# cap_touch.net
KiCad netlist of a schematic drawn in EAGLE
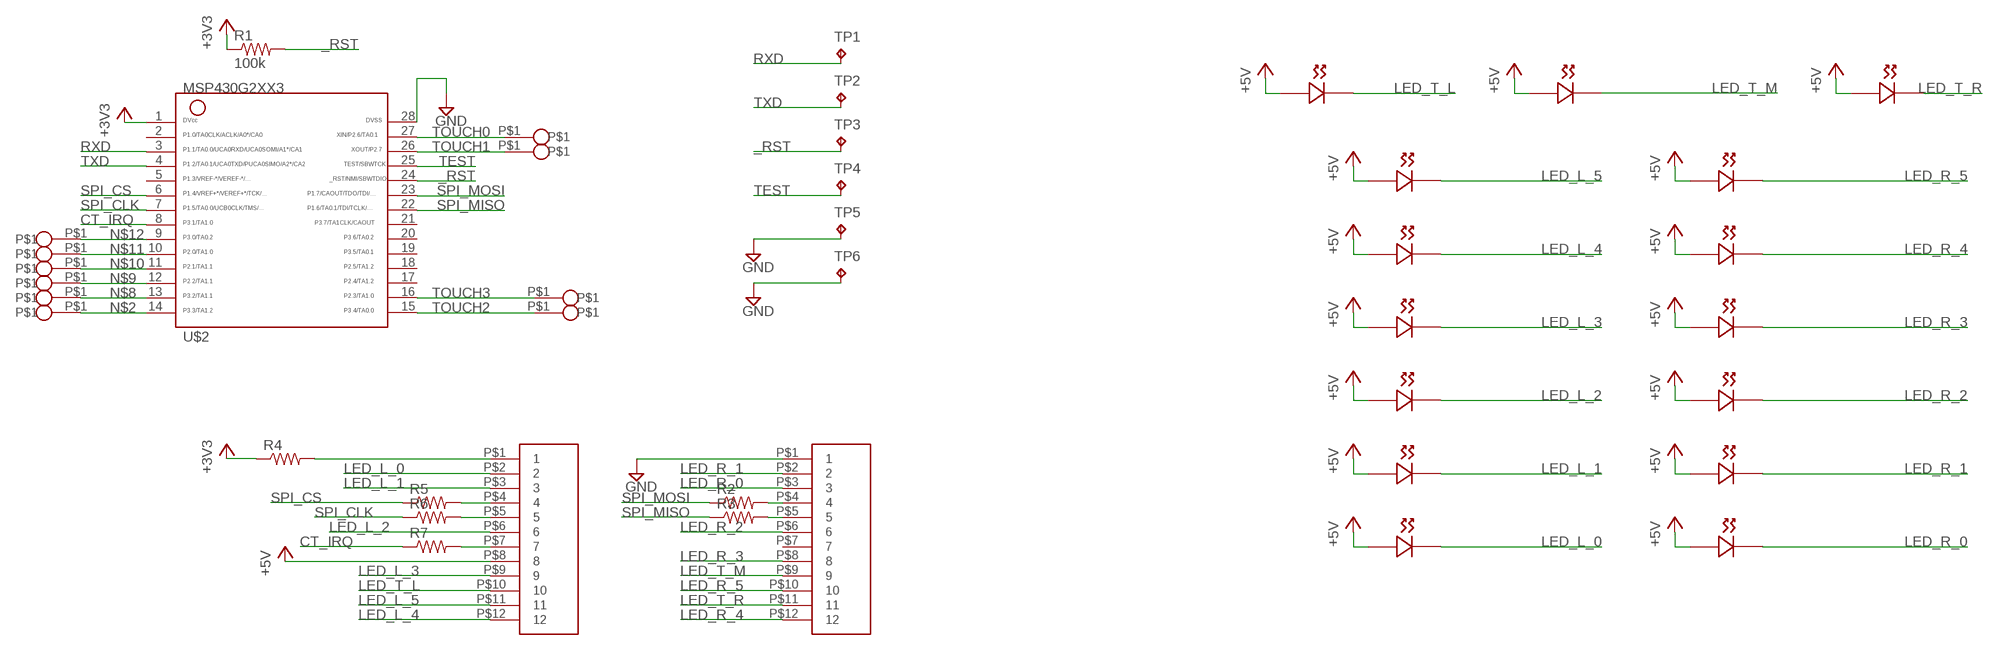
[diagram p0: schematic, sheet 1]

(export (version "E")
  (design (tool "Eeschema 10.0.6"))
  (components
    (comp (ref "R1")
      (value "100k")
      (footprint "eagle-import:0603-RES")
      (libsource (lib "eagle-import") (part "RESISTOR0603-RES"))
    )
    (comp (ref "R2")
      (value "RESISTOR0805-RES")
      (footprint "eagle-import:0805")
      (libsource (lib "eagle-import") (part "SparkFun-Resistors_RESISTOR0805-RES"))
    )
    (comp (ref "R3")
      (value "RESISTOR0805-RES")
      (footprint "eagle-import:0805")
      (libsource (lib "eagle-import") (part "SparkFun-Resistors_RESISTOR0805-RES"))
    )
    (comp (ref "R4")
      (value "RESISTOR0805-RES")
      (footprint "eagle-import:0805")
      (libsource (lib "eagle-import") (part "SparkFun-Resistors_RESISTOR0805-RES"))
    )
    (comp (ref "R5")
      (value "RESISTOR0805-RES")
      (footprint "eagle-import:0805")
      (libsource (lib "eagle-import") (part "SparkFun-Resistors_RESISTOR0805-RES"))
    )
    (comp (ref "R6")
      (value "RESISTOR0805-RES")
      (footprint "eagle-import:0805")
      (libsource (lib "eagle-import") (part "SparkFun-Resistors_RESISTOR0805-RES"))
    )
    (comp (ref "R7")
      (value "RESISTOR0805-RES")
      (footprint "eagle-import:0805")
      (libsource (lib "eagle-import") (part "SparkFun-Resistors_RESISTOR0805-RES"))
    )
    (comp (ref "TP1")
      (value "TPTP18SQ")
      (footprint "eagle-import:TP18SQ")
      (libsource (lib "eagle-import") (part "TPTP18SQ"))
    )
    (comp (ref "TP2")
      (value "TPTP18SQ")
      (footprint "eagle-import:TP18SQ")
      (libsource (lib "eagle-import") (part "TPTP18SQ"))
    )
    (comp (ref "TP3")
      (value "TPTP18SQ")
      (footprint "eagle-import:TP18SQ")
      (libsource (lib "eagle-import") (part "TPTP18SQ"))
    )
    (comp (ref "TP4")
      (value "TPTP18SQ")
      (footprint "eagle-import:TP18SQ")
      (libsource (lib "eagle-import") (part "TPTP18SQ"))
    )
    (comp (ref "TP5")
      (value "TPTP18SQ")
      (footprint "eagle-import:TP18SQ")
      (libsource (lib "eagle-import") (part "TPTP18SQ"))
    )
    (comp (ref "TP6")
      (value "TPTP18SQ")
      (footprint "eagle-import:TP18SQ")
      (libsource (lib "eagle-import") (part "TPTP18SQ"))
    )
    (comp (ref "U$1")
      (value "12_PIN_SMT_HEADER")
      (footprint "eagle-import:SMT_12PIN_HEADER")
      (libsource (lib "eagle-import") (part "12_PIN_SMT_HEADER"))
    )
    (comp (ref "U$2")
      (value "G2XX3---PW28")
      (footprint "eagle-import:PW28")
      (libsource (lib "eagle-import") (part "G2XX3---PW28"))
    )
    (comp (ref "U$3")
      (value "12_PIN_SMT_HEADER")
      (footprint "eagle-import:SMT_12PIN_HEADER")
      (libsource (lib "eagle-import") (part "12_PIN_SMT_HEADER"))
    )
    (comp (ref "U$8")
      (value "597-6601-607F")
      (footprint "eagle-import:597-6601-607F")
      (libsource (lib "eagle-import") (part "597-6601-607F"))
    )
    (comp (ref "U$9")
      (value "597-6601-607F")
      (footprint "eagle-import:597-6601-607F")
      (libsource (lib "eagle-import") (part "597-6601-607F"))
    )
    (comp (ref "U$10")
      (value "597-6601-607F")
      (footprint "eagle-import:597-6601-607F")
      (libsource (lib "eagle-import") (part "597-6601-607F"))
    )
    (comp (ref "U$11")
      (value "597-6601-607F")
      (footprint "eagle-import:597-6601-607F")
      (libsource (lib "eagle-import") (part "597-6601-607F"))
    )
    (comp (ref "U$12")
      (value "597-6601-607F")
      (footprint "eagle-import:597-6601-607F")
      (libsource (lib "eagle-import") (part "597-6601-607F"))
    )
    (comp (ref "U$13")
      (value "597-6601-607F")
      (footprint "eagle-import:597-6601-607F")
      (libsource (lib "eagle-import") (part "597-6601-607F"))
    )
    (comp (ref "U$14")
      (value "597-6601-607F")
      (footprint "eagle-import:597-6601-607F")
      (libsource (lib "eagle-import") (part "597-6601-607F"))
    )
    (comp (ref "U$15")
      (value "597-6601-607F")
      (footprint "eagle-import:597-6601-607F")
      (libsource (lib "eagle-import") (part "597-6601-607F"))
    )
    (comp (ref "U$16")
      (value "597-6601-607F")
      (footprint "eagle-import:597-6601-607F")
      (libsource (lib "eagle-import") (part "597-6601-607F"))
    )
    (comp (ref "U$17")
      (value "597-6601-607F")
      (footprint "eagle-import:597-6601-607F")
      (libsource (lib "eagle-import") (part "597-6601-607F"))
    )
    (comp (ref "U$18")
      (value "597-6601-607F")
      (footprint "eagle-import:597-6601-607F")
      (libsource (lib "eagle-import") (part "597-6601-607F"))
    )
    (comp (ref "U$19")
      (value "597-6601-607F")
      (footprint "eagle-import:597-6601-607F")
      (libsource (lib "eagle-import") (part "597-6601-607F"))
    )
    (comp (ref "U$20")
      (value "597-6601-607F")
      (footprint "eagle-import:597-6601-607F")
      (libsource (lib "eagle-import") (part "597-6601-607F"))
    )
    (comp (ref "U$21")
      (value "597-6601-607F")
      (footprint "eagle-import:597-6601-607F")
      (libsource (lib "eagle-import") (part "597-6601-607F"))
    )
    (comp (ref "U$22")
      (value "597-6601-607F")
      (footprint "eagle-import:597-6601-607F")
      (libsource (lib "eagle-import") (part "597-6601-607F"))
    )
    (comp (ref "U$25")
      (value "VIA")
      (footprint "eagle-import:VIA")
      (libsource (lib "eagle-import") (part "VIA"))
    )
    (comp (ref "U$26")
      (value "VIA")
      (footprint "eagle-import:VIA")
      (libsource (lib "eagle-import") (part "VIA"))
    )
    (comp (ref "U$27")
      (value "VIA")
      (footprint "eagle-import:VIA")
      (libsource (lib "eagle-import") (part "VIA"))
    )
    (comp (ref "U$28")
      (value "VIA")
      (footprint "eagle-import:VIA")
      (libsource (lib "eagle-import") (part "VIA"))
    )
    (comp (ref "U$29")
      (value "VIA")
      (footprint "eagle-import:VIA")
      (libsource (lib "eagle-import") (part "VIA"))
    )
    (comp (ref "U$30")
      (value "VIA")
      (footprint "eagle-import:VIA")
      (libsource (lib "eagle-import") (part "VIA"))
    )
    (comp (ref "U$31")
      (value "VIA")
      (footprint "eagle-import:VIA")
      (libsource (lib "eagle-import") (part "VIA"))
    )
    (comp (ref "U$32")
      (value "VIA")
      (footprint "eagle-import:VIA")
      (libsource (lib "eagle-import") (part "VIA"))
    )
    (comp (ref "U$33")
      (value "VIA")
      (footprint "eagle-import:VIA")
      (libsource (lib "eagle-import") (part "VIA"))
    )
    (comp (ref "U$34")
      (value "VIA")
      (footprint "eagle-import:VIA")
      (libsource (lib "eagle-import") (part "VIA"))
    )
  )
  (nets
    (net (code "1") (name "+3V3") (class "Default")
      (node (ref "R1") (pin "1") (pinfunction "1_1") (pintype "passive"))
      (node (ref "R4") (pin "1") (pinfunction "1_1") (pintype "passive"))
      (node (ref "U$2") (pin "1") (pinfunction "1_1") (pintype "bidirectional"))
    )
    (net (code "2") (name "+5V") (class "Default")
      (node (ref "U$1") (pin "P$8") (pinfunction "8_P$8") (pintype "bidirectional"))
      (node (ref "U$10") (pin "+") (pinfunction "R.POS_+") (pintype "bidirectional"))
      (node (ref "U$11") (pin "+") (pinfunction "R.POS_+") (pintype "bidirectional"))
      (node (ref "U$12") (pin "+") (pinfunction "R.POS_+") (pintype "bidirectional"))
      (node (ref "U$13") (pin "+") (pinfunction "R.POS_+") (pintype "bidirectional"))
      (node (ref "U$14") (pin "+") (pinfunction "R.POS_+") (pintype "bidirectional"))
      (node (ref "U$15") (pin "+") (pinfunction "R.POS_+") (pintype "bidirectional"))
      (node (ref "U$16") (pin "+") (pinfunction "R.POS_+") (pintype "bidirectional"))
      (node (ref "U$17") (pin "+") (pinfunction "R.POS_+") (pintype "bidirectional"))
      (node (ref "U$18") (pin "+") (pinfunction "R.POS_+") (pintype "bidirectional"))
      (node (ref "U$19") (pin "+") (pinfunction "R.POS_+") (pintype "bidirectional"))
      (node (ref "U$20") (pin "+") (pinfunction "R.POS_+") (pintype "bidirectional"))
      (node (ref "U$21") (pin "+") (pinfunction "R.POS_+") (pintype "bidirectional"))
      (node (ref "U$22") (pin "+") (pinfunction "R.POS_+") (pintype "bidirectional"))
      (node (ref "U$8") (pin "+") (pinfunction "R.POS_+") (pintype "bidirectional"))
      (node (ref "U$9") (pin "+") (pinfunction "R.POS_+") (pintype "bidirectional"))
    )
    (net (code "3") (name "/CT_IRQ") (class "Default")
      (node (ref "R7") (pin "1") (pinfunction "1_1") (pintype "passive"))
      (node (ref "U$2") (pin "8") (pinfunction "8_8") (pintype "bidirectional"))
    )
    (net (code "4") (name "/LED_L_0") (class "Default")
      (node (ref "U$1") (pin "P$2") (pinfunction "2_P$2") (pintype "bidirectional"))
      (node (ref "U$21") (pin "-") (pinfunction "R.NEG_-") (pintype "bidirectional"))
    )
    (net (code "5") (name "/LED_L_1") (class "Default")
      (node (ref "U$1") (pin "P$3") (pinfunction "3_P$3") (pintype "bidirectional"))
      (node (ref "U$19") (pin "-") (pinfunction "R.NEG_-") (pintype "bidirectional"))
    )
    (net (code "6") (name "/LED_L_2") (class "Default")
      (node (ref "U$1") (pin "P$6") (pinfunction "6_P$6") (pintype "bidirectional"))
      (node (ref "U$17") (pin "-") (pinfunction "R.NEG_-") (pintype "bidirectional"))
    )
    (net (code "7") (name "/LED_L_3") (class "Default")
      (node (ref "U$1") (pin "P$9") (pinfunction "9_P$9") (pintype "bidirectional"))
      (node (ref "U$15") (pin "-") (pinfunction "R.NEG_-") (pintype "bidirectional"))
    )
    (net (code "8") (name "/LED_L_4") (class "Default")
      (node (ref "U$1") (pin "P$12") (pinfunction "12_P$12") (pintype "bidirectional"))
      (node (ref "U$13") (pin "-") (pinfunction "R.NEG_-") (pintype "bidirectional"))
    )
    (net (code "9") (name "/LED_L_5") (class "Default")
      (node (ref "U$1") (pin "P$11") (pinfunction "11_P$11") (pintype "bidirectional"))
      (node (ref "U$11") (pin "-") (pinfunction "R.NEG_-") (pintype "bidirectional"))
    )
    (net (code "10") (name "/LED_R_0") (class "Default")
      (node (ref "U$22") (pin "-") (pinfunction "R.NEG_-") (pintype "bidirectional"))
      (node (ref "U$3") (pin "P$3") (pinfunction "3_P$3") (pintype "bidirectional"))
    )
    (net (code "11") (name "/LED_R_1") (class "Default")
      (node (ref "U$20") (pin "-") (pinfunction "R.NEG_-") (pintype "bidirectional"))
      (node (ref "U$3") (pin "P$2") (pinfunction "2_P$2") (pintype "bidirectional"))
    )
    (net (code "12") (name "/LED_R_2") (class "Default")
      (node (ref "U$18") (pin "-") (pinfunction "R.NEG_-") (pintype "bidirectional"))
      (node (ref "U$3") (pin "P$6") (pinfunction "6_P$6") (pintype "bidirectional"))
    )
    (net (code "13") (name "/LED_R_3") (class "Default")
      (node (ref "U$16") (pin "-") (pinfunction "R.NEG_-") (pintype "bidirectional"))
      (node (ref "U$3") (pin "P$8") (pinfunction "8_P$8") (pintype "bidirectional"))
    )
    (net (code "14") (name "/LED_R_4") (class "Default")
      (node (ref "U$14") (pin "-") (pinfunction "R.NEG_-") (pintype "bidirectional"))
      (node (ref "U$3") (pin "P$12") (pinfunction "12_P$12") (pintype "bidirectional"))
    )
    (net (code "15") (name "/LED_R_5") (class "Default")
      (node (ref "U$12") (pin "-") (pinfunction "R.NEG_-") (pintype "bidirectional"))
      (node (ref "U$3") (pin "P$10") (pinfunction "10_P$10") (pintype "bidirectional"))
    )
    (net (code "16") (name "/LED_T_L") (class "Default")
      (node (ref "U$1") (pin "P$10") (pinfunction "10_P$10") (pintype "bidirectional"))
      (node (ref "U$8") (pin "-") (pinfunction "R.NEG_-") (pintype "bidirectional"))
    )
    (net (code "17") (name "/LED_T_M") (class "Default")
      (node (ref "U$3") (pin "P$9") (pinfunction "9_P$9") (pintype "bidirectional"))
      (node (ref "U$9") (pin "-") (pinfunction "R.NEG_-") (pintype "bidirectional"))
    )
    (net (code "18") (name "/LED_T_R") (class "Default")
      (node (ref "U$10") (pin "-") (pinfunction "R.NEG_-") (pintype "bidirectional"))
      (node (ref "U$3") (pin "P$11") (pinfunction "11_P$11") (pintype "bidirectional"))
    )
    (net (code "19") (name "/N$2") (class "Default")
      (node (ref "U$2") (pin "14") (pinfunction "14_14") (pintype "bidirectional"))
      (node (ref "U$29") (pin "P$1") (pinfunction "P$1_P$1") (pintype "bidirectional"))
    )
    (net (code "20") (name "/N$8") (class "Default")
      (node (ref "U$2") (pin "13") (pinfunction "13_13") (pintype "bidirectional"))
      (node (ref "U$30") (pin "P$1") (pinfunction "P$1_P$1") (pintype "bidirectional"))
    )
    (net (code "21") (name "/N$9") (class "Default")
      (node (ref "U$2") (pin "12") (pinfunction "12_12") (pintype "bidirectional"))
      (node (ref "U$31") (pin "P$1") (pinfunction "P$1_P$1") (pintype "bidirectional"))
    )
    (net (code "22") (name "/N$10") (class "Default")
      (node (ref "U$2") (pin "11") (pinfunction "11_11") (pintype "bidirectional"))
      (node (ref "U$32") (pin "P$1") (pinfunction "P$1_P$1") (pintype "bidirectional"))
    )
    (net (code "23") (name "/N$11") (class "Default")
      (node (ref "U$2") (pin "10") (pinfunction "10_10") (pintype "bidirectional"))
      (node (ref "U$33") (pin "P$1") (pinfunction "P$1_P$1") (pintype "bidirectional"))
    )
    (net (code "24") (name "/N$12") (class "Default")
      (node (ref "U$2") (pin "9") (pinfunction "9_9") (pintype "bidirectional"))
      (node (ref "U$34") (pin "P$1") (pinfunction "P$1_P$1") (pintype "bidirectional"))
    )
    (net (code "25") (name "/RXD") (class "Default")
      (node (ref "TP1") (pin "TP") (pinfunction "TP_TP") (pintype "input"))
      (node (ref "U$2") (pin "3") (pinfunction "3_3") (pintype "bidirectional"))
    )
    (net (code "26") (name "/SPI_CLK") (class "Default")
      (node (ref "R6") (pin "1") (pinfunction "1_1") (pintype "passive"))
      (node (ref "U$2") (pin "7") (pinfunction "7_7") (pintype "bidirectional"))
    )
    (net (code "27") (name "/SPI_CS") (class "Default")
      (node (ref "R5") (pin "1") (pinfunction "1_1") (pintype "passive"))
      (node (ref "U$2") (pin "6") (pinfunction "6_6") (pintype "bidirectional"))
    )
    (net (code "28") (name "/SPI_MISO") (class "Default")
      (node (ref "R3") (pin "1") (pinfunction "1_1") (pintype "passive"))
      (node (ref "U$2") (pin "22") (pinfunction "22_22") (pintype "bidirectional"))
    )
    (net (code "29") (name "/SPI_MOSI") (class "Default")
      (node (ref "R2") (pin "1") (pinfunction "1_1") (pintype "passive"))
      (node (ref "U$2") (pin "23") (pinfunction "23_23") (pintype "bidirectional"))
    )
    (net (code "30") (name "/TEST") (class "Default")
      (node (ref "TP4") (pin "TP") (pinfunction "TP_TP") (pintype "input"))
      (node (ref "U$2") (pin "25") (pinfunction "25_25") (pintype "bidirectional"))
    )
    (net (code "31") (name "/TOUCH0") (class "Default")
      (node (ref "U$2") (pin "27") (pinfunction "27_27") (pintype "bidirectional"))
      (node (ref "U$26") (pin "P$1") (pinfunction "P$1_P$1") (pintype "bidirectional"))
    )
    (net (code "32") (name "/TOUCH1") (class "Default")
      (node (ref "U$2") (pin "26") (pinfunction "26_26") (pintype "bidirectional"))
      (node (ref "U$25") (pin "P$1") (pinfunction "P$1_P$1") (pintype "bidirectional"))
    )
    (net (code "33") (name "/TOUCH2") (class "Default")
      (node (ref "U$2") (pin "15") (pinfunction "15_15") (pintype "bidirectional"))
      (node (ref "U$28") (pin "P$1") (pinfunction "P$1_P$1") (pintype "bidirectional"))
    )
    (net (code "34") (name "/TOUCH3") (class "Default")
      (node (ref "U$2") (pin "16") (pinfunction "16_16") (pintype "bidirectional"))
      (node (ref "U$27") (pin "P$1") (pinfunction "P$1_P$1") (pintype "bidirectional"))
    )
    (net (code "35") (name "/TXD") (class "Default")
      (node (ref "TP2") (pin "TP") (pinfunction "TP_TP") (pintype "input"))
      (node (ref "U$2") (pin "4") (pinfunction "4_4") (pintype "bidirectional"))
    )
    (net (code "36") (name "/_RST") (class "Default")
      (node (ref "R1") (pin "2") (pinfunction "2_2") (pintype "passive"))
      (node (ref "TP3") (pin "TP") (pinfunction "TP_TP") (pintype "input"))
      (node (ref "U$2") (pin "24") (pinfunction "24_24") (pintype "bidirectional"))
    )
    (net (code "37") (name "GND") (class "Default")
      (node (ref "TP5") (pin "TP") (pinfunction "TP_TP") (pintype "input"))
      (node (ref "TP6") (pin "TP") (pinfunction "TP_TP") (pintype "input"))
      (node (ref "U$2") (pin "28") (pinfunction "28_28") (pintype "bidirectional"))
      (node (ref "U$3") (pin "P$1") (pinfunction "1_P$1") (pintype "bidirectional"))
    )
    (net (code "38") (name "Net-(U$1-1)") (class "Default")
      (node (ref "R4") (pin "2") (pinfunction "2_2") (pintype "passive"))
      (node (ref "U$1") (pin "P$1") (pinfunction "1_P$1") (pintype "bidirectional"))
    )
    (net (code "39") (name "Net-(U$1-4)") (class "Default")
      (node (ref "R5") (pin "2") (pinfunction "2_2") (pintype "passive"))
      (node (ref "U$1") (pin "P$4") (pinfunction "4_P$4") (pintype "bidirectional"))
    )
    (net (code "40") (name "Net-(U$1-5)") (class "Default")
      (node (ref "R6") (pin "2") (pinfunction "2_2") (pintype "passive"))
      (node (ref "U$1") (pin "P$5") (pinfunction "5_P$5") (pintype "bidirectional"))
    )
    (net (code "41") (name "Net-(U$1-7)") (class "Default")
      (node (ref "R7") (pin "2") (pinfunction "2_2") (pintype "passive"))
      (node (ref "U$1") (pin "P$7") (pinfunction "7_P$7") (pintype "bidirectional"))
    )
    (net (code "42") (name "Net-(U$3-4)") (class "Default")
      (node (ref "R2") (pin "2") (pinfunction "2_2") (pintype "passive"))
      (node (ref "U$3") (pin "P$4") (pinfunction "4_P$4") (pintype "bidirectional"))
    )
    (net (code "43") (name "Net-(U$3-5)") (class "Default")
      (node (ref "R3") (pin "2") (pinfunction "2_2") (pintype "passive"))
      (node (ref "U$3") (pin "P$5") (pinfunction "5_P$5") (pintype "bidirectional"))
    )
    (net (code "44") (name "unconnected-(U$2-Pad2)") (class "Default")
      (node (ref "U$2") (pin "2") (pinfunction "2_2") (pintype "bidirectional"))
    )
    (net (code "45") (name "unconnected-(U$2-Pad5)") (class "Default")
      (node (ref "U$2") (pin "5") (pinfunction "5_5") (pintype "bidirectional"))
    )
    (net (code "46") (name "unconnected-(U$2-Pad17)") (class "Default")
      (node (ref "U$2") (pin "17") (pinfunction "17_17") (pintype "bidirectional"))
    )
    (net (code "47") (name "unconnected-(U$2-Pad18)") (class "Default")
      (node (ref "U$2") (pin "18") (pinfunction "18_18") (pintype "bidirectional"))
    )
    (net (code "48") (name "unconnected-(U$2-Pad19)") (class "Default")
      (node (ref "U$2") (pin "19") (pinfunction "19_19") (pintype "bidirectional"))
    )
    (net (code "49") (name "unconnected-(U$2-Pad20)") (class "Default")
      (node (ref "U$2") (pin "20") (pinfunction "20_20") (pintype "bidirectional"))
    )
    (net (code "50") (name "unconnected-(U$2-Pad21)") (class "Default")
      (node (ref "U$2") (pin "21") (pinfunction "21_21") (pintype "bidirectional"))
    )
    (net (code "51") (name "unconnected-(U$3-7-PadP$7)") (class "Default")
      (node (ref "U$3") (pin "P$7") (pinfunction "7_P$7") (pintype "bidirectional"))
    )
  )
)
